# main.net
KiCad netlist of a schematic drawn in Altium Designer
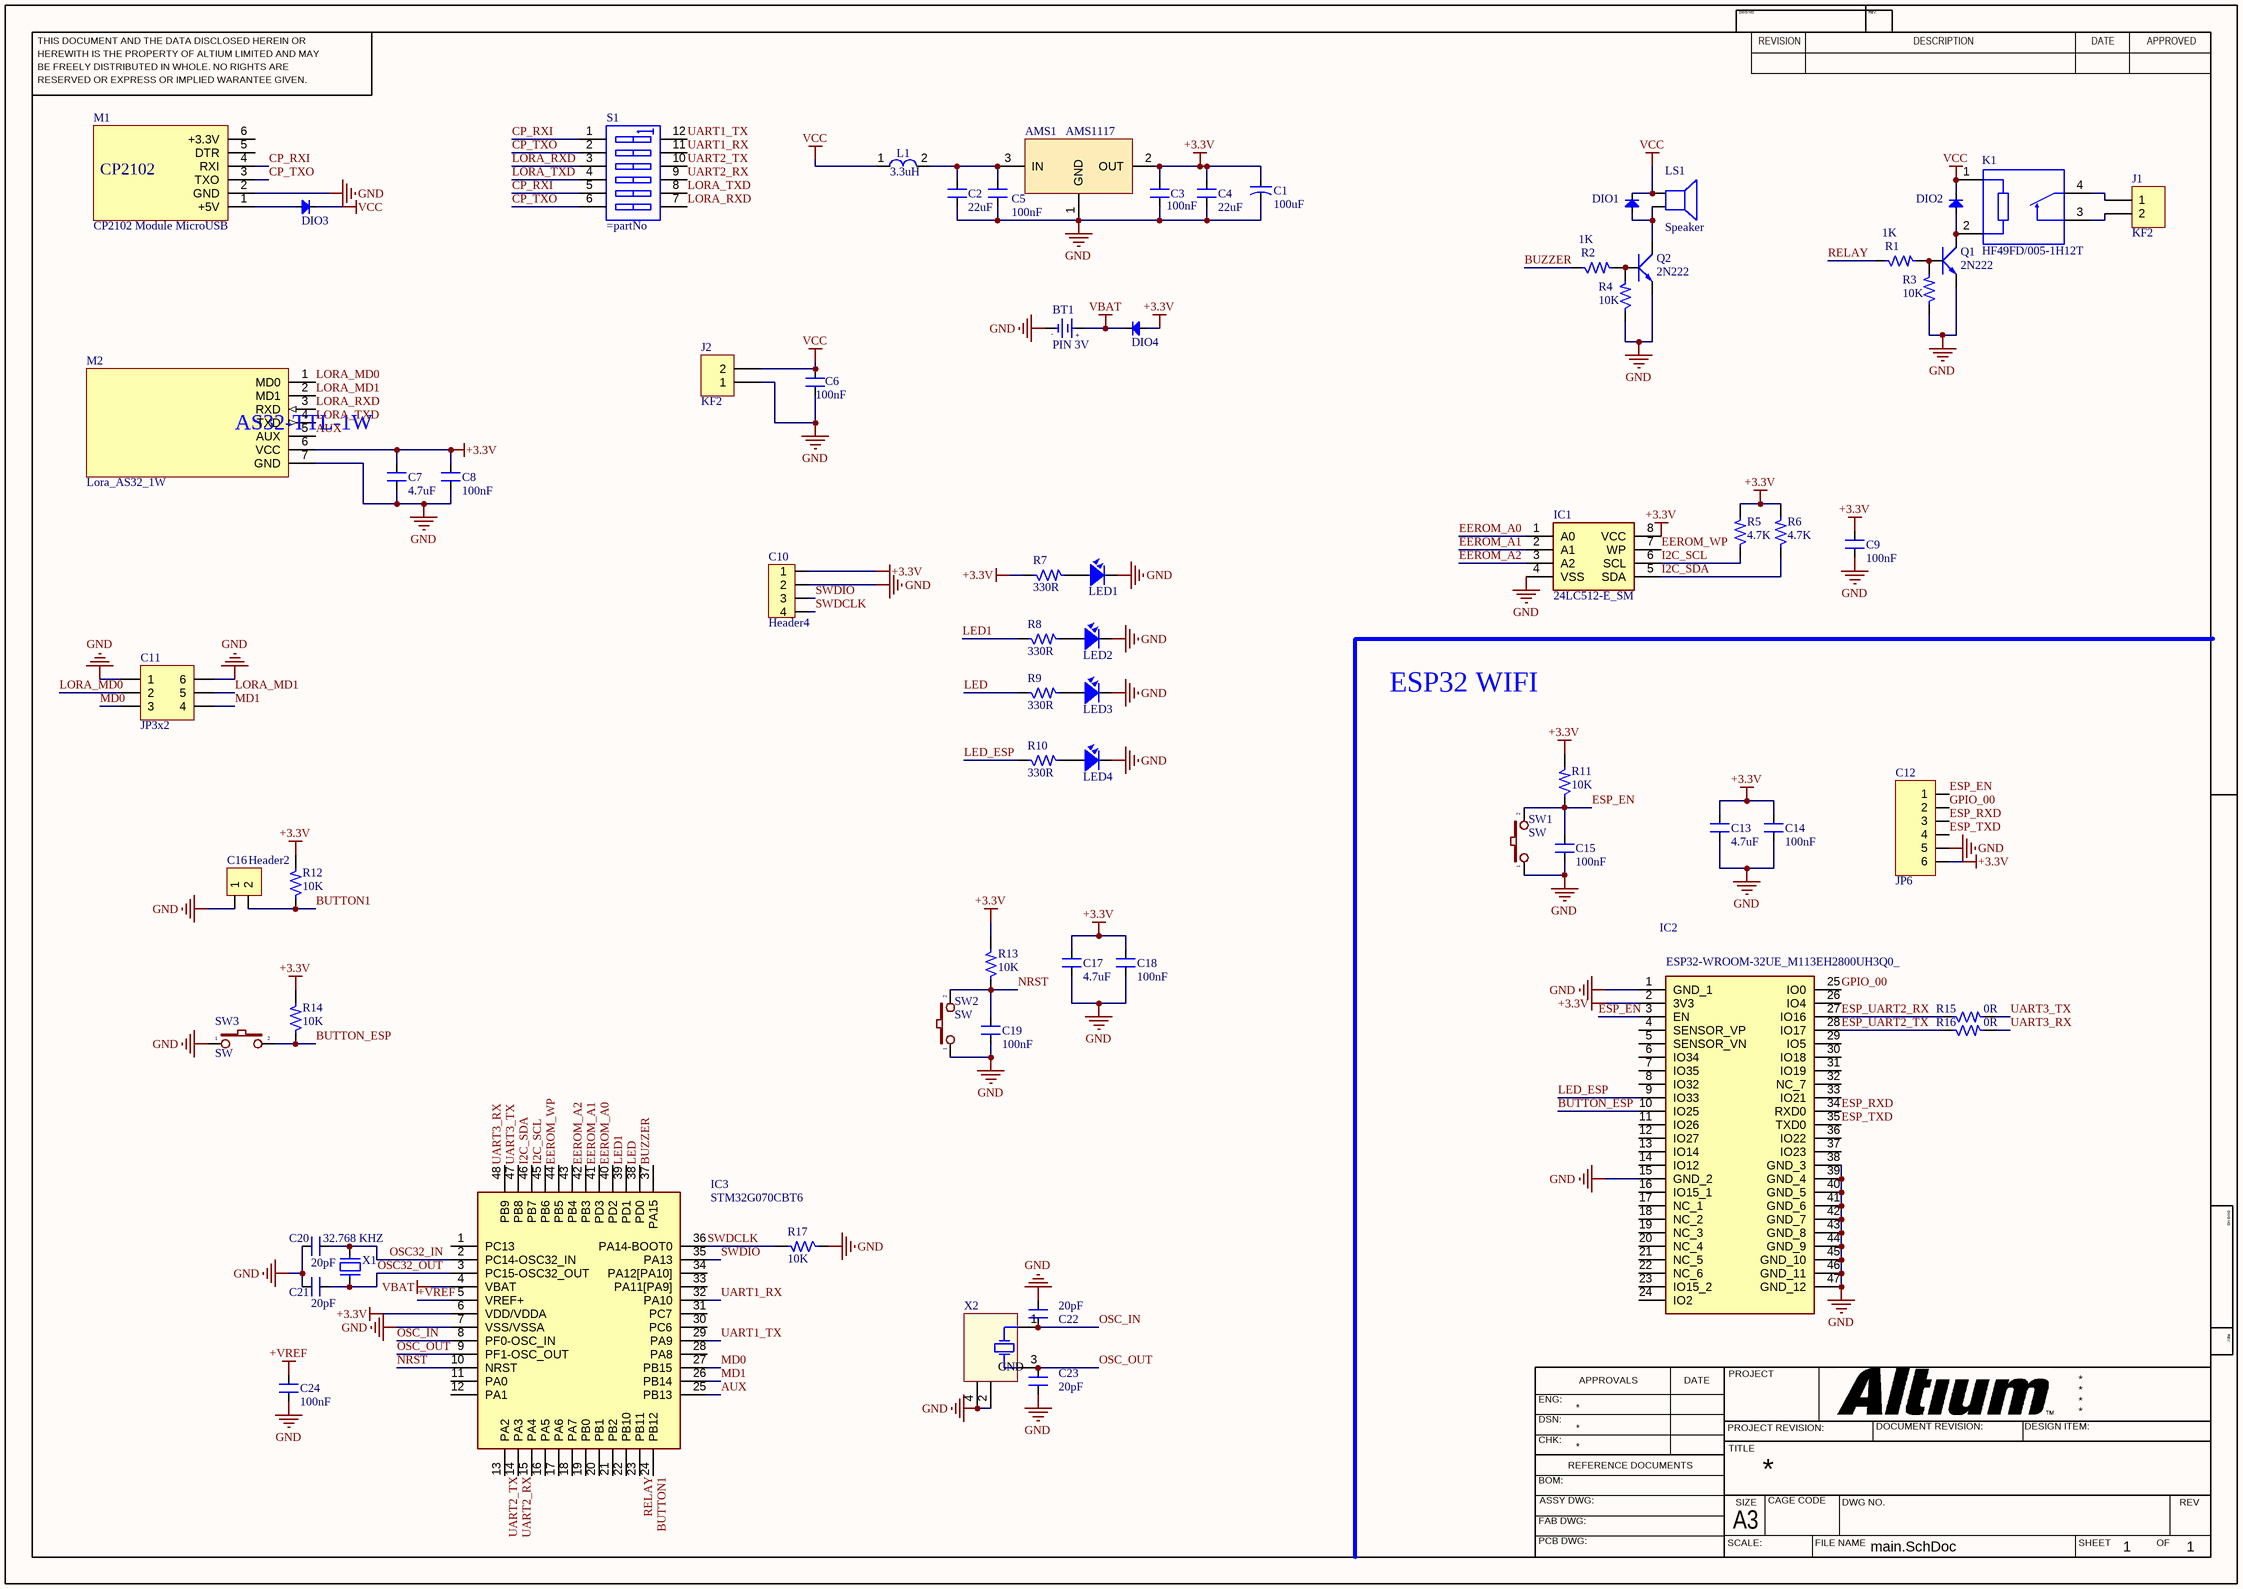
[diagram p0: main.SchDoc]

(export (version "E")
  (design (tool "Eeschema 10.0.6"))
  (components
    (comp (ref "AMS1") (value "AMS1117") (footprint "SOT223_N") (libsource (lib "SamacSys") (part "AMS1117")))
    (comp (ref "BT1")
      (value "PIN 3V")
      (footprint "PIN3V")
      (description "Battery 3VDC")
      (libsource (lib "LIBRARY") (part "PIN 3V"))
    )
    (comp (ref "C1")
      (value "100uF")
      (footprint "CA-ALU-5")
      (description "Capacitor (Semiconductor SIM Model)")
      (fields (field (name "PUBLISHER") "Altium Limited"))
      (libsource (lib "thu vien 3d") (part "CN-ALU-DIP"))
    )
    (comp (ref "C2")
      (value "22uF")
      (footprint "CAP_0805")
      (description "22µF ±20% 25V Ceramic Capacitor X5R 0805 (2012 Metric)")
      (fields
        (field (name "MANUFACTURER") "Murata Electronics")
        (field (name "MANUFACTURER PART NUMBER") "GRM21BR61E226ME44K")
      )
      (libsource (lib "EsteemPCB_SOM_Course_schlib") (part "CAP_22uF-25V-20%-0805"))
    )
    (comp (ref "C3")
      (value "100nF")
      (footprint "CAP_0603")
      (description "0.1µF ±10% 10V Ceramic Capacitor X7R 0603 (1608 Metric)")
      (fields
        (field (name "MANUFACTURER") "Yageo")
        (field (name "MANUFACTURER PART NUMBER") "CC0603KRX7R6BB104")
      )
      (libsource (lib "EsteemPCB_SOM_Course_schlib") (part "CAP_100nF-10V-5%-0603"))
    )
    (comp (ref "C4")
      (value "22uF")
      (footprint "CAP_0805")
      (description "22µF ±20% 25V Ceramic Capacitor X5R 0805 (2012 Metric)")
      (fields
        (field (name "MANUFACTURER") "Murata Electronics")
        (field (name "MANUFACTURER PART NUMBER") "GRM21BR61E226ME44K")
      )
      (libsource (lib "EsteemPCB_SOM_Course_schlib") (part "CAP_22uF-25V-20%-0805"))
    )
    (comp (ref "C5")
      (value "100nF")
      (footprint "CAP_0603")
      (description "0.1µF ±10% 10V Ceramic Capacitor X7R 0603 (1608 Metric)")
      (fields
        (field (name "MANUFACTURER") "Yageo")
        (field (name "MANUFACTURER PART NUMBER") "CC0603KRX7R6BB104")
      )
      (libsource (lib "EsteemPCB_SOM_Course_schlib") (part "CAP_100nF-10V-5%-0603"))
    )
    (comp (ref "C6") (value "100nF") (footprint "CN2.5") (libsource (lib "thu vien 3d") (part "CN")))
    (comp (ref "C7")
      (value "4.7uF")
      (footprint "CAP_0603")
      (description "4.7µF ±10% 16V Ceramic Capacitor X5R 0603 (1608 Metric)")
      (fields
        (field (name "MANUFACTURER") "Murata Electronics")
        (field (name "MANUFACTURER PART NUMBER") "GRM188R61C475KAAJD")
      )
      (libsource (lib "EsteemPCB_SOM_Course_schlib") (part "CAP_4.7uF-16V-10%-0603"))
    )
    (comp (ref "C8")
      (value "100nF")
      (footprint "CAP_0603")
      (description "0.1µF ±10% 10V Ceramic Capacitor X7R 0603 (1608 Metric)")
      (fields
        (field (name "MANUFACTURER") "Yageo")
        (field (name "MANUFACTURER PART NUMBER") "CC0603KRX7R6BB104")
      )
      (libsource (lib "EsteemPCB_SOM_Course_schlib") (part "CAP_100nF-10V-5%-0603"))
    )
    (comp (ref "C9")
      (value "100nF")
      (footprint "CAP_0603")
      (description "0.1µF ±10% 10V Ceramic Capacitor X7R 0603 (1608 Metric)")
      (fields
        (field (name "MANUFACTURER") "Yageo")
        (field (name "MANUFACTURER PART NUMBER") "CC0603KRX7R6BB104")
      )
      (libsource (lib "EsteemPCB_SOM_Course_schlib") (part "CAP_100nF-10V-5%-0603"))
    )
    (comp (ref "C10")
      (value "Header4")
      (footprint "Header4")
      (description "Header IDC, 4 x 1 Pin Vertical 2.54mm Pitch (Non-Boxed, Male)")
      (fields
        (field (name "MANUFACTURER") "Würth Elektronik eiSos GmbH")
        (field (name "PARTNO") "613002143121")
        (field (name "CREATED BY") "Karrer Zheng")
      )
      (libsource (lib "thu vien 3d") (part "Header4"))
    )
    (comp (ref "C11")
      (value "JP3x2")
      (footprint "JP3-D2T")
      (description "WR-PHD 2.54 mm Dual Socket Header")
      (fields
        (field (name "MANUFACTURER") "Würth Elektronik eiSos GmbH")
        (field (name "PARTNO") "61300621821")
        (field (name "CREATED BY") "Karrer Zheng")
      )
      (libsource (lib "thu vien 3d") (part "JP3x2"))
    )
    (comp (ref "C12")
      (value "JP6")
      (footprint "JP6-C1T")
      (description "WR-PHD 2.54 mm Angled Socket Header")
      (fields
        (field (name "MANUFACTURER") "Würth Elektronik eiSos GmbH")
        (field (name "PARTNO") "613006143121")
        (field (name "CREATED BY") "Karrer Zheng")
      )
      (libsource (lib "LIBRARY") (part "JP6"))
    )
    (comp (ref "C13")
      (value "4.7uF")
      (footprint "CAP_0603")
      (description "4.7µF ±10% 16V Ceramic Capacitor X5R 0603 (1608 Metric)")
      (fields
        (field (name "MANUFACTURER") "Murata Electronics")
        (field (name "MANUFACTURER PART NUMBER") "GRM188R61C475KAAJD")
      )
      (libsource (lib "EsteemPCB_SOM_Course_schlib") (part "CAP_4.7uF-16V-10%-0603"))
    )
    (comp (ref "C14")
      (value "100nF")
      (footprint "CAP_0603")
      (description "0.1µF ±10% 10V Ceramic Capacitor X7R 0603 (1608 Metric)")
      (fields
        (field (name "MANUFACTURER") "Yageo")
        (field (name "MANUFACTURER PART NUMBER") "CC0603KRX7R6BB104")
      )
      (libsource (lib "EsteemPCB_SOM_Course_schlib") (part "CAP_100nF-10V-5%-0603"))
    )
    (comp (ref "C15")
      (value "100nF")
      (footprint "CAP_0603")
      (description "0.1µF ±10% 10V Ceramic Capacitor X7R 0603 (1608 Metric)")
      (fields
        (field (name "MANUFACTURER") "Yageo")
        (field (name "MANUFACTURER PART NUMBER") "CC0603KRX7R6BB104")
      )
      (libsource (lib "EsteemPCB_SOM_Course_schlib") (part "CAP_100nF-10V-5%-0603"))
    )
    (comp (ref "C16")
      (value "Header2")
      (footprint "Header2")
      (description "Header IDC, 2 x 1 Pin Vertical 2.54mm Pitch (Non-Boxed, Male)")
      (fields
        (field (name "MANUFACTURER") "Würth Elektronik eiSos GmbH")
        (field (name "PARTNO") "613002143121")
        (field (name "CREATED BY") "Karrer Zheng")
      )
      (libsource (lib "LIBRARY") (part "Header2"))
    )
    (comp (ref "C17")
      (value "4.7uF")
      (footprint "CAP_0603")
      (description "4.7µF ±10% 16V Ceramic Capacitor X5R 0603 (1608 Metric)")
      (fields
        (field (name "MANUFACTURER") "Murata Electronics")
        (field (name "MANUFACTURER PART NUMBER") "GRM188R61C475KAAJD")
      )
      (libsource (lib "EsteemPCB_SOM_Course_schlib") (part "CAP_4.7uF-16V-10%-0603"))
    )
    (comp (ref "C18")
      (value "100nF")
      (footprint "CAP_0603")
      (description "0.1µF ±10% 10V Ceramic Capacitor X7R 0603 (1608 Metric)")
      (fields
        (field (name "MANUFACTURER") "Yageo")
        (field (name "MANUFACTURER PART NUMBER") "CC0603KRX7R6BB104")
      )
      (libsource (lib "EsteemPCB_SOM_Course_schlib") (part "CAP_100nF-10V-5%-0603"))
    )
    (comp (ref "C19")
      (value "100nF")
      (footprint "CAP_0603")
      (description "0.1µF ±10% 10V Ceramic Capacitor X7R 0603 (1608 Metric)")
      (fields
        (field (name "MANUFACTURER") "Yageo")
        (field (name "MANUFACTURER PART NUMBER") "CC0603KRX7R6BB104")
      )
      (libsource (lib "EsteemPCB_SOM_Course_schlib") (part "CAP_100nF-10V-5%-0603"))
    )
    (comp (ref "C20")
      (value "20pF")
      (footprint "CAP_0603")
      (description "1000pF ±10% 10V Ceramic Capacitor X7R 0603 (1608 Metric)")
      (fields
        (field (name "MANUFACTURER") "Yageo")
        (field (name "MANUFACTURER PART NUMBER") "CC0603KRX7R6BB102")
      )
      (libsource (lib "EsteemPCB_SOM_Course_schlib") (part "CAP_1nF-10V-10%-0603"))
    )
    (comp (ref "C21")
      (value "20pF")
      (footprint "CAP_0603")
      (description "1000pF ±10% 10V Ceramic Capacitor X7R 0603 (1608 Metric)")
      (fields
        (field (name "MANUFACTURER") "Yageo")
        (field (name "MANUFACTURER PART NUMBER") "CC0603KRX7R6BB102")
      )
      (libsource (lib "EsteemPCB_SOM_Course_schlib") (part "CAP_1nF-10V-10%-0603"))
    )
    (comp (ref "C22")
      (value "20pF")
      (footprint "CAP_0603")
      (description "1000pF ±10% 10V Ceramic Capacitor X7R 0603 (1608 Metric)")
      (fields
        (field (name "MANUFACTURER") "Yageo")
        (field (name "MANUFACTURER PART NUMBER") "CC0603KRX7R6BB102")
      )
      (libsource (lib "EsteemPCB_SOM_Course_schlib") (part "CAP_1nF-10V-10%-0603"))
    )
    (comp (ref "C23")
      (value "20pF")
      (footprint "CAP_0603")
      (description "1000pF ±10% 10V Ceramic Capacitor X7R 0603 (1608 Metric)")
      (fields
        (field (name "MANUFACTURER") "Yageo")
        (field (name "MANUFACTURER PART NUMBER") "CC0603KRX7R6BB102")
      )
      (libsource (lib "EsteemPCB_SOM_Course_schlib") (part "CAP_1nF-10V-10%-0603"))
    )
    (comp (ref "C24")
      (value "100nF")
      (footprint "CAP_0603")
      (description "0.1µF ±10% 10V Ceramic Capacitor X7R 0603 (1608 Metric)")
      (fields
        (field (name "MANUFACTURER") "Yageo")
        (field (name "MANUFACTURER PART NUMBER") "CC0603KRX7R6BB104")
      )
      (libsource (lib "EsteemPCB_SOM_Course_schlib") (part "CAP_100nF-10V-5%-0603"))
    )
    (comp (ref "DIO1")
      (value "Diode SMD")
      (footprint "DIO-SMD-123")
      (description "Default Diode")
      (fields (field (name "PUBLISHER") "Altium Limited"))
      (libsource (lib "LIBRARY") (part "Diode SMD"))
    )
    (comp (ref "DIO2")
      (value "Diode SMD")
      (footprint "DIO-SMD-123")
      (description "Default Diode")
      (fields (field (name "PUBLISHER") "Altium Limited"))
      (libsource (lib "LIBRARY") (part "Diode SMD"))
    )
    (comp (ref "DIO3")
      (value "Diode SMD")
      (footprint "DIO-SMD-123")
      (description "Default Diode")
      (fields (field (name "PUBLISHER") "Altium Limited"))
      (libsource (lib "LIBRARY") (part "Diode SMD"))
    )
    (comp (ref "DIO4")
      (value "Diode SMD")
      (footprint "DIO-SMD-123")
      (description "Default Diode")
      (fields (field (name "PUBLISHER") "Altium Limited"))
      (libsource (lib "LIBRARY") (part "Diode SMD"))
    )
    (comp (ref "IC1")
      (value "24LC512-E_SM")
      (footprint "SamacSys:SOIC127P794X203-8N")
      (description "Integrated Circuit")
      (fields
        (field (name "MANUFACTURER_PART_NUMBER") "24LC512-E/SM")
        (field (name "MOUSER PART NUMBER") "579-24LC512-E/SM")
      )
      (libsource (lib "*") (part "24LC512-E_SM"))
    )
    (comp (ref "IC2")
      (value "ESP32-WROOM-32UE_M113EH2800UH3Q0_")
      (footprint "SamacSys:ESP32WROOM32UEM113EH2800UH3Q0")
      (description "Integrated Circuit")
      (fields
        (field (name "MANUFACTURER_PART_NUMBER") "ESP32-WROOM-32UE(M113EH2800UH3Q0)")
        (field (name "MOUSER PART NUMBER") "356-ESP32WRM32UE28UH")
      )
      (libsource (lib "*") (part "ESP32-WROOM-32UE_M113EH2800UH3Q0_"))
    )
    (comp (ref "IC3")
      (value "STM32G070CBT6")
      (footprint "SamacSys:QFP50P900X900X160-48N")
      (description "Integrated Circuit")
      (fields (field (name "MOUSER PART NUMBER") "511-STM32G070CBT6"))
      (libsource (lib "*") (part "STM32G070CBT6"))
    )
    (comp (ref "J1")
      (value "KF2")
      (footprint "KF2-5.08")
      (fields
        (field (name "MANUFACTURER") "Würth Elektronik eiSos GmbH")
        (field (name "PARTNO") "691103110002")
        (field (name "CREATED BY") "Karrer Zheng")
      )
      (libsource (lib "") (part "KF2_1"))
    )
    (comp (ref "J2")
      (value "KF2")
      (footprint "KF2-5.08")
      (fields
        (field (name "MANUFACTURER") "Würth Elektronik eiSos GmbH")
        (field (name "PARTNO") "691103110002")
        (field (name "CREATED BY") "Karrer Zheng")
      )
      (libsource (lib "LIBRARY") (part "KF2"))
    )
    (comp (ref "K1")
      (value "HF49FD/005-1H12T")
      (footprint "RELAY_HF49FD/005-1H12T")
      (description "Relay: electromagnetic; SPST-NO; Ucoil: 5VDC; 5A/250VAC; 5A/30VDC")
      (fields (field (name "MF") "Hongfa"))
      (libsource (lib "HF49FD_005-1H12T") (part "HF49FD/005-1H12T"))
    )
    (comp (ref "L1")
      (value "3.3uH")
      (footprint "L-SMD-M-7.3x4.5")
      (fields
        (field (name "PARTNO") "78477010")
        (field (name "MANUFACTURER") "Wurth Elektronik")
        (field (name "CREATED BY") "Baojun Chen")
      )
      (libsource (lib "thu vien 3d") (part "L-SMD-1"))
    )
    (comp (ref "LED1")
      (value "LED")
      (footprint "LED-3MM-RED")
      (description "LED Single colour Green and Red")
      (libsource (lib "LIBRARY") (part "LED"))
    )
    (comp (ref "LED2")
      (value "LED")
      (footprint "LED-3MM-GREEN")
      (description "LED Single colour Green and Red")
      (libsource (lib "LIBRARY") (part "LED"))
    )
    (comp (ref "LED3")
      (value "LED")
      (footprint "LED-3MM-GREEN")
      (description "LED Single colour Green and Red")
      (libsource (lib "LIBRARY") (part "LED"))
    )
    (comp (ref "LED4")
      (value "LED")
      (footprint "LED-3MM-GREEN")
      (description "LED Single colour Green and Red")
      (libsource (lib "LIBRARY") (part "LED"))
    )
    (comp (ref "LS1")
      (value "Speaker")
      (footprint "SPEAKER")
      (description "Loudspeaker")
      (fields (field (name "PUBLISHER") "Altium Limited"))
      (libsource (lib "LIBRARY") (part "Speaker"))
    )
    (comp (ref "M1")
      (value "CP2102 Module MicroUSB")
      (footprint "CP2102 Module")
      (libsource (lib "SamacSys") (part "CP2102 Module MicroUSB"))
    )
    (comp (ref "M2")
      (value "Lora_AS32_1W")
      (footprint "LORA_AS32-TTL-1W")
      (libsource (lib "SamacSys") (part "Lora_AS32_1W"))
    )
    (comp (ref "Q1")
      (value "2N222")
      (footprint "SOT23-231")
      (description "NPN 600mW, ECB")
      (libsource (lib "LIBRARY") (part "2N222"))
    )
    (comp (ref "Q2")
      (value "2N222")
      (footprint "SOT23-231")
      (description "NPN 600mW, ECB")
      (libsource (lib "LIBRARY") (part "2N222"))
    )
    (comp (ref "R1")
      (value "1K")
      (footprint "RES_0603")
      (description "1 kOhms ±1% 0.1W, 1/10W Chip Resistor 0603 (1608 Metric) Thick Film")
      (fields
        (field (name "MANUFACTURER") "Yageo")
        (field (name "MANUFACTURER PART NUMBER") "RC0603FR-071KL")
      )
      (libsource (lib "EsteemPCB_SOM_Course_schlib") (part "RES_1K-0.1W-1%-0603"))
    )
    (comp (ref "R2")
      (value "1K")
      (footprint "RES_0603")
      (description "1 kOhms ±1% 0.1W, 1/10W Chip Resistor 0603 (1608 Metric) Thick Film")
      (fields
        (field (name "MANUFACTURER") "Yageo")
        (field (name "MANUFACTURER PART NUMBER") "RC0603FR-071KL")
      )
      (libsource (lib "EsteemPCB_SOM_Course_schlib") (part "RES_1K-0.1W-1%-0603"))
    )
    (comp (ref "R3")
      (value "10K")
      (footprint "RES_0603")
      (description "10 kOhms ±1% 0.1W, 1/10W Chip Resistor 0603 (1608 Metric) Thick Film")
      (fields
        (field (name "MANUFACTURER") "Yageo")
        (field (name "MANUFACTURER PART NUMBER") "RC0603FR-0710KL")
      )
      (libsource (lib "EsteemPCB_SOM_Course_schlib") (part "RES_10K-0.1W-1%-0603"))
    )
    (comp (ref "R4")
      (value "10K")
      (footprint "RES_0603")
      (description "10 kOhms ±1% 0.1W, 1/10W Chip Resistor 0603 (1608 Metric) Thick Film")
      (fields
        (field (name "MANUFACTURER") "Yageo")
        (field (name "MANUFACTURER PART NUMBER") "RC0603FR-0710KL")
      )
      (libsource (lib "EsteemPCB_SOM_Course_schlib") (part "RES_10K-0.1W-1%-0603"))
    )
    (comp (ref "R5")
      (value "4.7K")
      (footprint "RES_0603")
      (fields
        (field (name "MANUFACTURER") "Panasonic Electronic Components")
        (field (name "MANUFACTURER PART NUMBER") "ERJ-3RQF3R3V")
      )
      (libsource (lib "EsteemPCB_SOM_Course_schlib") (part "RES_3.3R-0.1W-1%-0603"))
    )
    (comp (ref "R6")
      (value "4.7K")
      (footprint "RES_0603")
      (fields
        (field (name "MANUFACTURER") "Panasonic Electronic Components")
        (field (name "MANUFACTURER PART NUMBER") "ERJ-3RQF3R3V")
      )
      (libsource (lib "EsteemPCB_SOM_Course_schlib") (part "RES_3.3R-0.1W-1%-0603"))
    )
    (comp (ref "R7")
      (value "330R")
      (footprint "RES_0603")
      (fields
        (field (name "MANUFACTURER") "Panasonic Electronic Components")
        (field (name "MANUFACTURER PART NUMBER") "ERJ-3RQF3R3V")
      )
      (libsource (lib "EsteemPCB_SOM_Course_schlib") (part "RES_3.3R-0.1W-1%-0603"))
    )
    (comp (ref "R8")
      (value "330R")
      (footprint "RES_0603")
      (fields
        (field (name "MANUFACTURER") "Panasonic Electronic Components")
        (field (name "MANUFACTURER PART NUMBER") "ERJ-3RQF3R3V")
      )
      (libsource (lib "EsteemPCB_SOM_Course_schlib") (part "RES_3.3R-0.1W-1%-0603"))
    )
    (comp (ref "R9")
      (value "330R")
      (footprint "RES_0603")
      (fields
        (field (name "MANUFACTURER") "Panasonic Electronic Components")
        (field (name "MANUFACTURER PART NUMBER") "ERJ-3RQF3R3V")
      )
      (libsource (lib "EsteemPCB_SOM_Course_schlib") (part "RES_3.3R-0.1W-1%-0603"))
    )
    (comp (ref "R10")
      (value "330R")
      (footprint "RES_0603")
      (fields
        (field (name "MANUFACTURER") "Panasonic Electronic Components")
        (field (name "MANUFACTURER PART NUMBER") "ERJ-3RQF3R3V")
      )
      (libsource (lib "EsteemPCB_SOM_Course_schlib") (part "RES_3.3R-0.1W-1%-0603"))
    )
    (comp (ref "R11")
      (value "10K")
      (footprint "RES_0603")
      (description "10 kOhms ±1% 0.1W, 1/10W Chip Resistor 0603 (1608 Metric) Thick Film")
      (fields
        (field (name "MANUFACTURER") "Yageo")
        (field (name "MANUFACTURER PART NUMBER") "RC0603FR-0710KL")
      )
      (libsource (lib "EsteemPCB_SOM_Course_schlib") (part "RES_10K-0.1W-1%-0603"))
    )
    (comp (ref "R12")
      (value "10K")
      (footprint "RES_0603")
      (description "10 kOhms ±1% 0.1W, 1/10W Chip Resistor 0603 (1608 Metric) Thick Film")
      (fields
        (field (name "MANUFACTURER") "Yageo")
        (field (name "MANUFACTURER PART NUMBER") "RC0603FR-0710KL")
      )
      (libsource (lib "EsteemPCB_SOM_Course_schlib") (part "RES_10K-0.1W-1%-0603"))
    )
    (comp (ref "R13")
      (value "10K")
      (footprint "RES_0603")
      (description "1 kOhms ±1% 0.1W, 1/10W Chip Resistor 0603 (1608 Metric) Thick Film")
      (fields
        (field (name "MANUFACTURER") "Yageo")
        (field (name "MANUFACTURER PART NUMBER") "RC0603FR-071KL")
      )
      (libsource (lib "EsteemPCB_SOM_Course_schlib") (part "RES_1K-0.1W-1%-0603"))
    )
    (comp (ref "R14")
      (value "10K")
      (footprint "RES_0603")
      (description "10 kOhms ±1% 0.1W, 1/10W Chip Resistor 0603 (1608 Metric) Thick Film")
      (fields
        (field (name "MANUFACTURER") "Yageo")
        (field (name "MANUFACTURER PART NUMBER") "RC0603FR-0710KL")
      )
      (libsource (lib "EsteemPCB_SOM_Course_schlib") (part "RES_10K-0.1W-1%-0603"))
    )
    (comp (ref "R15")
      (value "0R")
      (footprint "RES_0603")
      (description "0 Ohms Jumper 0.1W, 1/10W Chip Resistor 0603 (1608 Metric) Thick Film")
      (fields
        (field (name "MANUFACTURER") "Yageo")
        (field (name "MANUFACTURER PART NUMBER") "RC0603JR-070RL")
      )
      (libsource (lib "EsteemPCB_SOM_Course_schlib") (part "RES_0R-0.1W-1%-0603"))
    )
    (comp (ref "R16")
      (value "0R")
      (footprint "RES_0603")
      (description "0 Ohms Jumper 0.1W, 1/10W Chip Resistor 0603 (1608 Metric) Thick Film")
      (fields
        (field (name "MANUFACTURER") "Yageo")
        (field (name "MANUFACTURER PART NUMBER") "RC0603JR-070RL")
      )
      (libsource (lib "EsteemPCB_SOM_Course_schlib") (part "RES_0R-0.1W-1%-0603"))
    )
    (comp (ref "R17")
      (value "10K")
      (footprint "RES_0603")
      (description "1 kOhms ±1% 0.1W, 1/10W Chip Resistor 0603 (1608 Metric) Thick Film")
      (fields
        (field (name "MANUFACTURER") "Yageo")
        (field (name "MANUFACTURER PART NUMBER") "RC0603FR-071KL")
      )
      (libsource (lib "EsteemPCB_SOM_Course_schlib") (part "RES_1K-0.1W-1%-0603"))
    )
    (comp (ref "S1")
      (value "~")
      (footprint "SW-DIP6")
      (description "WS-DITV 2.54 mm small compact THT flat actuator with top tape")
      (fields
        (field (name "MANUFACTURER") "Wurth Elektronik")
        (field (name "PART NO.") "418127160906")
        (field (name "CREATED BY") "Baojun Chen")
      )
      (libsource (lib "LIBRARY") (part "SWDIP6"))
    )
    (comp (ref "SW1")
      (value "SW")
      (footprint "SW1-SMD")
      (description "Switch button 2 pin")
      (libsource (lib "LIBRARY") (part "SW2"))
    )
    (comp (ref "SW2")
      (value "SW")
      (footprint "SW1-SMD")
      (description "Switch button 2 pin")
      (libsource (lib "LIBRARY") (part "SW2"))
    )
    (comp (ref "SW3")
      (value "SW")
      (footprint "SW1-SMD")
      (description "Switch button 2 pin")
      (libsource (lib "LIBRARY") (part "SW2"))
    )
    (comp (ref "X1")
      (value "32.768 KHZ")
      (footprint "XT2-32.768KHz-2_V")
      (description "Crystal, 32.768 KHz, -40 to 85 degC, 3.2 x 1.5 x 0.9 mm SMD")
      (libsource (lib "LIBRARY") (part "XT2"))
    )
    (comp (ref "X2")
      (value "XT4")
      (footprint "XT4-16.000MHz-4_V")
      (description "Crystal, 16 MHz, -30 to 85 degC, 3.2 x 2.5 x 0.9 mm SMD")
      (libsource (lib "LIBRARY") (part "XT4"))
    )
  )
  (nets
    (net (code "1") (name "+3.3V") (class "Default")
      (node (ref "AMS1") (pin "2") (pinfunction "OUT_2") (pintype "passive"))
      (node (ref "C1") (pin "1") (pinfunction "1_1") (pintype "passive"))
      (node (ref "C10") (pin "1") (pinfunction "1_1") (pintype "passive"))
      (node (ref "C12") (pin "6") (pinfunction "6_6") (pintype "passive"))
      (node (ref "C13") (pin "2") (pinfunction "2_2") (pintype "passive"))
      (node (ref "C14") (pin "2") (pinfunction "2_2") (pintype "passive"))
      (node (ref "C17") (pin "2") (pinfunction "2_2") (pintype "passive"))
      (node (ref "C18") (pin "2") (pinfunction "2_2") (pintype "passive"))
      (node (ref "C3") (pin "2") (pinfunction "2_2") (pintype "passive"))
      (node (ref "C4") (pin "2") (pinfunction "2_2") (pintype "passive"))
      (node (ref "C7") (pin "2") (pinfunction "2_2") (pintype "passive"))
      (node (ref "C8") (pin "2") (pinfunction "2_2") (pintype "passive"))
      (node (ref "C9") (pin "2") (pinfunction "2_2") (pintype "passive"))
      (node (ref "DIO4") (pin "1") (pinfunction "A_1") (pintype "passive"))
      (node (ref "IC1") (pin "8") (pinfunction "VCC_8") (pintype "passive"))
      (node (ref "IC2") (pin "2") (pinfunction "3V3_2") (pintype "passive"))
      (node (ref "IC3") (pin "6") (pinfunction "VDD/VDDA_6") (pintype "passive"))
      (node (ref "M2") (pin "6") (pinfunction "VCC_6") (pintype "power_in"))
      (node (ref "R11") (pin "2") (pinfunction "2_2") (pintype "passive"))
      (node (ref "R12") (pin "2") (pinfunction "2_2") (pintype "passive"))
      (node (ref "R13") (pin "2") (pinfunction "2_2") (pintype "passive"))
      (node (ref "R14") (pin "2") (pinfunction "2_2") (pintype "passive"))
      (node (ref "R5") (pin "2") (pinfunction "2_2") (pintype "passive"))
      (node (ref "R6") (pin "2") (pinfunction "2_2") (pintype "passive"))
      (node (ref "R7") (pin "1") (pinfunction "1_1") (pintype "passive"))
    )
    (net (code "2") (name "+VREF") (class "Default")
      (node (ref "C24") (pin "2") (pinfunction "2_2") (pintype "passive"))
      (node (ref "IC3") (pin "5") (pinfunction "VREF+_5") (pintype "passive"))
    )
    (net (code "3") (name "/AUX") (class "Default")
      (node (ref "IC3") (pin "25") (pinfunction "PB13_25") (pintype "passive"))
      (node (ref "M2") (pin "5") (pinfunction "AUX_5") (pintype "passive"))
    )
    (net (code "4") (name "/BUTTON1") (class "Default")
      (node (ref "C16") (pin "2") (pinfunction "2_2") (pintype "passive"))
      (node (ref "IC3") (pin "24") (pinfunction "PB12_24") (pintype "passive"))
      (node (ref "R12") (pin "1") (pinfunction "1_1") (pintype "passive"))
    )
    (net (code "5") (name "/BUTTON_ESP") (class "Default")
      (node (ref "IC2") (pin "10") (pinfunction "IO25_10") (pintype "passive"))
      (node (ref "R14") (pin "1") (pinfunction "1_1") (pintype "passive"))
      (node (ref "SW3") (pin "2") (pinfunction "2_2") (pintype "passive"))
    )
    (net (code "6") (name "/BUZZER") (class "Default")
      (node (ref "IC3") (pin "37") (pinfunction "PA15_37") (pintype "passive"))
      (node (ref "R2") (pin "1") (pinfunction "1_1") (pintype "passive"))
    )
    (net (code "7") (name "/CP_RXI") (class "Default")
      (node (ref "M1") (pin "4") (pinfunction "RXI_4") (pintype "passive"))
      (node (ref "S1") (pin "1") (pinfunction "1_1") (pintype "passive"))
      (node (ref "S1") (pin "5") (pinfunction "5_5") (pintype "passive"))
    )
    (net (code "8") (name "/CP_TXO") (class "Default")
      (node (ref "M1") (pin "3") (pinfunction "TXO_3") (pintype "passive"))
      (node (ref "S1") (pin "2") (pinfunction "2_2") (pintype "passive"))
      (node (ref "S1") (pin "6") (pinfunction "6_6") (pintype "passive"))
    )
    (net (code "9") (name "/EEROM_A0") (class "Default")
      (node (ref "IC1") (pin "1") (pinfunction "A0_1") (pintype "passive"))
      (node (ref "IC3") (pin "40") (pinfunction "PD2_40") (pintype "passive"))
    )
    (net (code "10") (name "/EEROM_A1") (class "Default")
      (node (ref "IC1") (pin "2") (pinfunction "A1_2") (pintype "passive"))
      (node (ref "IC3") (pin "41") (pinfunction "PD3_41") (pintype "passive"))
    )
    (net (code "11") (name "/EEROM_A2") (class "Default")
      (node (ref "IC1") (pin "3") (pinfunction "A2_3") (pintype "passive"))
      (node (ref "IC3") (pin "42") (pinfunction "PB3_42") (pintype "passive"))
    )
    (net (code "12") (name "/EEROM_WP") (class "Default")
      (node (ref "IC1") (pin "7") (pinfunction "WP_7") (pintype "passive"))
      (node (ref "IC3") (pin "44") (pinfunction "PB5_44") (pintype "passive"))
    )
    (net (code "13") (name "/ESP_EN") (class "Default")
      (node (ref "C12") (pin "1") (pinfunction "1_1") (pintype "passive"))
      (node (ref "C15") (pin "2") (pinfunction "2_2") (pintype "passive"))
      (node (ref "IC2") (pin "3") (pinfunction "EN_3") (pintype "passive"))
      (node (ref "R11") (pin "1") (pinfunction "1_1") (pintype "passive"))
      (node (ref "SW1") (pin "2") (pinfunction "2_2") (pintype "passive"))
    )
    (net (code "14") (name "/ESP_RXD") (class "Default")
      (node (ref "C12") (pin "3") (pinfunction "3_3") (pintype "passive"))
      (node (ref "IC2") (pin "34") (pinfunction "RXD0_34") (pintype "passive"))
    )
    (net (code "15") (name "/ESP_TXD") (class "Default")
      (node (ref "C12") (pin "4") (pinfunction "4_4") (pintype "passive"))
      (node (ref "IC2") (pin "35") (pinfunction "TXD0_35") (pintype "passive"))
    )
    (net (code "16") (name "/ESP_UART2_RX") (class "Default")
      (node (ref "IC2") (pin "27") (pinfunction "IO16_27") (pintype "passive"))
      (node (ref "R15") (pin "1") (pinfunction "1_1") (pintype "passive"))
    )
    (net (code "17") (name "/ESP_UART2_TX") (class "Default")
      (node (ref "IC2") (pin "28") (pinfunction "IO17_28") (pintype "passive"))
      (node (ref "R16") (pin "1") (pinfunction "1_1") (pintype "passive"))
    )
    (net (code "18") (name "/GPIO_00") (class "Default")
      (node (ref "C12") (pin "2") (pinfunction "2_2") (pintype "passive"))
      (node (ref "IC2") (pin "25") (pinfunction "IO0_25") (pintype "passive"))
    )
    (net (code "19") (name "/I2C_SCL") (class "Default")
      (node (ref "IC1") (pin "6") (pinfunction "SCL_6") (pintype "passive"))
      (node (ref "IC3") (pin "45") (pinfunction "PB6_45") (pintype "passive"))
      (node (ref "R5") (pin "1") (pinfunction "1_1") (pintype "passive"))
    )
    (net (code "20") (name "/I2C_SDA") (class "Default")
      (node (ref "IC1") (pin "5") (pinfunction "SDA_5") (pintype "passive"))
      (node (ref "IC3") (pin "46") (pinfunction "PB7_46") (pintype "passive"))
      (node (ref "R6") (pin "1") (pinfunction "1_1") (pintype "passive"))
    )
    (net (code "21") (name "/LED") (class "Default")
      (node (ref "IC3") (pin "38") (pinfunction "PD0_38") (pintype "passive"))
      (node (ref "R9") (pin "1") (pinfunction "1_1") (pintype "passive"))
    )
    (net (code "22") (name "/LED1") (class "Default")
      (node (ref "IC3") (pin "39") (pinfunction "PD1_39") (pintype "passive"))
      (node (ref "R8") (pin "1") (pinfunction "1_1") (pintype "passive"))
    )
    (net (code "23") (name "/LED_ESP") (class "Default")
      (node (ref "IC2") (pin "9") (pinfunction "IO33_9") (pintype "passive"))
      (node (ref "R10") (pin "1") (pinfunction "1_1") (pintype "passive"))
    )
    (net (code "24") (name "/LORA_MD0") (class "Default")
      (node (ref "C11") (pin "2") (pinfunction "2_2") (pintype "passive"))
      (node (ref "M2") (pin "1") (pinfunction "MD0_1") (pintype "passive"))
    )
    (net (code "25") (name "/LORA_MD1") (class "Default")
      (node (ref "C11") (pin "5") (pinfunction "5_5") (pintype "passive"))
      (node (ref "M2") (pin "2") (pinfunction "MD1_2") (pintype "passive"))
    )
    (net (code "26") (name "/LORA_RXD") (class "Default")
      (node (ref "M2") (pin "3") (pinfunction "RXD_3") (pintype "input"))
      (node (ref "S1") (pin "3") (pinfunction "3_3") (pintype "passive"))
      (node (ref "S1") (pin "7") (pinfunction "7_7") (pintype "passive"))
    )
    (net (code "27") (name "/LORA_TXD") (class "Default")
      (node (ref "M2") (pin "4") (pinfunction "TXD_4") (pintype "output"))
      (node (ref "S1") (pin "4") (pinfunction "4_4") (pintype "passive"))
      (node (ref "S1") (pin "8") (pinfunction "8_8") (pintype "passive"))
    )
    (net (code "28") (name "/MD0") (class "Default")
      (node (ref "C11") (pin "3") (pinfunction "3_3") (pintype "passive"))
      (node (ref "IC3") (pin "27") (pinfunction "PB15_27") (pintype "passive"))
    )
    (net (code "29") (name "/MD1") (class "Default")
      (node (ref "C11") (pin "4") (pinfunction "4_4") (pintype "passive"))
      (node (ref "IC3") (pin "26") (pinfunction "PB14_26") (pintype "passive"))
    )
    (net (code "30") (name "/NRST") (class "Default")
      (node (ref "C19") (pin "2") (pinfunction "2_2") (pintype "passive"))
      (node (ref "IC3") (pin "10") (pinfunction "NRST_10") (pintype "passive"))
      (node (ref "R13") (pin "1") (pinfunction "1_1") (pintype "passive"))
      (node (ref "SW2") (pin "2") (pinfunction "2_2") (pintype "passive"))
    )
    (net (code "31") (name "/OSC32_IN") (class "Default")
      (node (ref "C20") (pin "2") (pinfunction "2_2") (pintype "passive"))
      (node (ref "IC3") (pin "2") (pinfunction "PC14-OSC32_IN_2") (pintype "passive"))
      (node (ref "X1") (pin "2") (pinfunction "2_2") (pintype "passive"))
    )
    (net (code "32") (name "/OSC32_OUT") (class "Default")
      (node (ref "C21") (pin "2") (pinfunction "2_2") (pintype "passive"))
      (node (ref "IC3") (pin "3") (pinfunction "PC15-OSC32_OUT_3") (pintype "passive"))
      (node (ref "X1") (pin "1") (pinfunction "1_1") (pintype "passive"))
    )
    (net (code "33") (name "/OSC_IN") (class "Default")
      (node (ref "C22") (pin "2") (pinfunction "2_2") (pintype "passive"))
      (node (ref "IC3") (pin "8") (pinfunction "PF0-OSC_IN_8") (pintype "passive"))
      (node (ref "X2") (pin "1") (pinfunction "XTAL_1") (pintype "passive"))
    )
    (net (code "34") (name "/OSC_OUT") (class "Default")
      (node (ref "C23") (pin "2") (pinfunction "2_2") (pintype "passive"))
      (node (ref "IC3") (pin "9") (pinfunction "PF1-OSC_OUT_9") (pintype "passive"))
      (node (ref "X2") (pin "3") (pinfunction "XTAL_3") (pintype "passive"))
    )
    (net (code "35") (name "/RELAY") (class "Default")
      (node (ref "IC3") (pin "23") (pinfunction "PB11_23") (pintype "passive"))
      (node (ref "R1") (pin "1") (pinfunction "1_1") (pintype "passive"))
    )
    (net (code "36") (name "/SWDCLK") (class "Default")
      (node (ref "C10") (pin "4") (pinfunction "4_4") (pintype "passive"))
      (node (ref "IC3") (pin "36") (pinfunction "PA14-BOOT0_36") (pintype "passive"))
      (node (ref "R17") (pin "2") (pinfunction "2_2") (pintype "passive"))
    )
    (net (code "37") (name "/SWDIO") (class "Default")
      (node (ref "C10") (pin "3") (pinfunction "3_3") (pintype "passive"))
      (node (ref "IC3") (pin "35") (pinfunction "PA13_35") (pintype "passive"))
    )
    (net (code "38") (name "/UART1_RX") (class "Default")
      (node (ref "IC3") (pin "32") (pinfunction "PA10_32") (pintype "passive"))
      (node (ref "S1") (pin "11") (pinfunction "11_11") (pintype "passive"))
    )
    (net (code "39") (name "/UART1_TX") (class "Default")
      (node (ref "IC3") (pin "29") (pinfunction "PA9_29") (pintype "passive"))
      (node (ref "S1") (pin "12") (pinfunction "12_12") (pintype "passive"))
    )
    (net (code "40") (name "/UART2_RX") (class "Default")
      (node (ref "IC3") (pin "14") (pinfunction "PA3_14") (pintype "passive"))
      (node (ref "S1") (pin "9") (pinfunction "9_9") (pintype "passive"))
    )
    (net (code "41") (name "/UART2_TX") (class "Default")
      (node (ref "IC3") (pin "13") (pinfunction "PA2_13") (pintype "passive"))
      (node (ref "S1") (pin "10") (pinfunction "10_10") (pintype "passive"))
    )
    (net (code "42") (name "/UART3_RX") (class "Default")
      (node (ref "IC3") (pin "48") (pinfunction "PB9_48") (pintype "passive"))
      (node (ref "R16") (pin "2") (pinfunction "2_2") (pintype "passive"))
    )
    (net (code "43") (name "/UART3_TX") (class "Default")
      (node (ref "IC3") (pin "47") (pinfunction "PB8_47") (pintype "passive"))
      (node (ref "R15") (pin "2") (pinfunction "2_2") (pintype "passive"))
    )
    (net (code "44") (name "GND") (class "Default")
      (node (ref "AMS1") (pin "1") (pinfunction "GND_1") (pintype "passive"))
      (node (ref "BT1") (pin "2") (pinfunction "GND_2") (pintype "passive"))
      (node (ref "C1") (pin "2") (pinfunction "2_2") (pintype "passive"))
      (node (ref "C10") (pin "2") (pinfunction "2_2") (pintype "passive"))
      (node (ref "C11") (pin "1") (pinfunction "1_1") (pintype "passive"))
      (node (ref "C11") (pin "6") (pinfunction "6_6") (pintype "passive"))
      (node (ref "C12") (pin "5") (pinfunction "5_5") (pintype "passive"))
      (node (ref "C13") (pin "1") (pinfunction "1_1") (pintype "passive"))
      (node (ref "C14") (pin "1") (pinfunction "1_1") (pintype "passive"))
      (node (ref "C15") (pin "1") (pinfunction "1_1") (pintype "passive"))
      (node (ref "C16") (pin "1") (pinfunction "1_1") (pintype "passive"))
      (node (ref "C17") (pin "1") (pinfunction "1_1") (pintype "passive"))
      (node (ref "C18") (pin "1") (pinfunction "1_1") (pintype "passive"))
      (node (ref "C19") (pin "1") (pinfunction "1_1") (pintype "passive"))
      (node (ref "C2") (pin "1") (pinfunction "1_1") (pintype "passive"))
      (node (ref "C20") (pin "1") (pinfunction "1_1") (pintype "passive"))
      (node (ref "C21") (pin "1") (pinfunction "1_1") (pintype "passive"))
      (node (ref "C22") (pin "1") (pinfunction "1_1") (pintype "passive"))
      (node (ref "C23") (pin "1") (pinfunction "1_1") (pintype "passive"))
      (node (ref "C24") (pin "1") (pinfunction "1_1") (pintype "passive"))
      (node (ref "C3") (pin "1") (pinfunction "1_1") (pintype "passive"))
      (node (ref "C4") (pin "1") (pinfunction "1_1") (pintype "passive"))
      (node (ref "C5") (pin "1") (pinfunction "1_1") (pintype "passive"))
      (node (ref "C6") (pin "1") (pinfunction "1_1") (pintype "passive"))
      (node (ref "C7") (pin "1") (pinfunction "1_1") (pintype "passive"))
      (node (ref "C8") (pin "1") (pinfunction "1_1") (pintype "passive"))
      (node (ref "C9") (pin "1") (pinfunction "1_1") (pintype "passive"))
      (node (ref "IC1") (pin "4") (pinfunction "VSS_4") (pintype "passive"))
      (node (ref "IC2") (pin "1") (pinfunction "GND_1_1") (pintype "passive"))
      (node (ref "IC2") (pin "15") (pinfunction "GND_2_15") (pintype "passive"))
      (node (ref "IC2") (pin "38") (pinfunction "GND_3_38") (pintype "passive"))
      (node (ref "IC2") (pin "39") (pinfunction "GND_4_39") (pintype "passive"))
      (node (ref "IC2") (pin "40") (pinfunction "GND_5_40") (pintype "passive"))
      (node (ref "IC2") (pin "41") (pinfunction "GND_6_41") (pintype "passive"))
      (node (ref "IC2") (pin "42") (pinfunction "GND_7_42") (pintype "passive"))
      (node (ref "IC2") (pin "43") (pinfunction "GND_8_43") (pintype "passive"))
      (node (ref "IC2") (pin "44") (pinfunction "GND_9_44") (pintype "passive"))
      (node (ref "IC2") (pin "45") (pinfunction "GND_10_45") (pintype "passive"))
      (node (ref "IC2") (pin "46") (pinfunction "GND_11_46") (pintype "passive"))
      (node (ref "IC2") (pin "47") (pinfunction "GND_12_47") (pintype "passive"))
      (node (ref "IC3") (pin "7") (pinfunction "VSS/VSSA_7") (pintype "passive"))
      (node (ref "J2") (pin "1") (pinfunction "1_1") (pintype "passive"))
      (node (ref "LED1") (pin "2") (pinfunction "2_2") (pintype "passive"))
      (node (ref "LED2") (pin "2") (pinfunction "2_2") (pintype "passive"))
      (node (ref "LED3") (pin "2") (pinfunction "2_2") (pintype "passive"))
      (node (ref "LED4") (pin "2") (pinfunction "2_2") (pintype "passive"))
      (node (ref "M1") (pin "2") (pinfunction "GND_2") (pintype "passive"))
      (node (ref "M2") (pin "7") (pinfunction "GND_7") (pintype "power_in"))
      (node (ref "Q1") (pin "1") (pinfunction "E_1") (pintype "passive"))
      (node (ref "Q2") (pin "1") (pinfunction "E_1") (pintype "passive"))
      (node (ref "R17") (pin "1") (pinfunction "1_1") (pintype "passive"))
      (node (ref "R3") (pin "1") (pinfunction "1_1") (pintype "passive"))
      (node (ref "R4") (pin "1") (pinfunction "1_1") (pintype "passive"))
      (node (ref "SW1") (pin "1") (pinfunction "1_1") (pintype "passive"))
      (node (ref "SW2") (pin "1") (pinfunction "1_1") (pintype "passive"))
      (node (ref "SW3") (pin "1") (pinfunction "1_1") (pintype "passive"))
      (node (ref "X2") (pin "2") (pinfunction "GND_2") (pintype "power_in"))
      (node (ref "X2") (pin "4") (pinfunction "GND_4") (pintype "power_in"))
    )
    (net (code "45") (name "Net-(AMS1-IN)") (class "Default")
      (node (ref "AMS1") (pin "3") (pinfunction "IN_3") (pintype "passive"))
      (node (ref "C2") (pin "2") (pinfunction "2_2") (pintype "passive"))
      (node (ref "C5") (pin "2") (pinfunction "2_2") (pintype "passive"))
      (node (ref "L1") (pin "2") (pinfunction "2_2") (pintype "passive"))
    )
    (net (code "46") (name "Net-(DIO1-A)") (class "Default")
      (node (ref "DIO1") (pin "1") (pinfunction "A_1") (pintype "passive"))
      (node (ref "LS1") (pin "2") (pinfunction "2_2") (pintype "passive"))
      (node (ref "Q2") (pin "3") (pinfunction "C_3") (pintype "passive"))
    )
    (net (code "47") (name "Net-(DIO2-A)") (class "Default")
      (node (ref "DIO2") (pin "1") (pinfunction "A_1") (pintype "passive"))
      (node (ref "K1") (pin "2") (pinfunction "L2_2") (pintype "passive"))
      (node (ref "Q1") (pin "3") (pinfunction "C_3") (pintype "passive"))
    )
    (net (code "48") (name "Net-(DIO3-A)") (class "Default")
      (node (ref "DIO3") (pin "1") (pinfunction "A_1") (pintype "passive"))
      (node (ref "M1") (pin "1") (pinfunction "+5V_1") (pintype "passive"))
    )
    (net (code "49") (name "Net-(K1-C1)") (class "Default")
      (node (ref "J1") (pin "1") (pinfunction "1_1") (pintype "passive"))
      (node (ref "K1") (pin "4") (pinfunction "C1_4") (pintype "passive"))
    )
    (net (code "50") (name "Net-(K1-C2)") (class "Default")
      (node (ref "J1") (pin "2") (pinfunction "2_2") (pintype "passive"))
      (node (ref "K1") (pin "3") (pinfunction "C2_3") (pintype "passive"))
    )
    (net (code "51") (name "Net-(LED1-Pad1)") (class "Default")
      (node (ref "LED1") (pin "1") (pinfunction "1_1") (pintype "passive"))
      (node (ref "R7") (pin "2") (pinfunction "2_2") (pintype "passive"))
    )
    (net (code "52") (name "Net-(LED2-Pad1)") (class "Default")
      (node (ref "LED2") (pin "1") (pinfunction "1_1") (pintype "passive"))
      (node (ref "R8") (pin "2") (pinfunction "2_2") (pintype "passive"))
    )
    (net (code "53") (name "Net-(LED3-Pad1)") (class "Default")
      (node (ref "LED3") (pin "1") (pinfunction "1_1") (pintype "passive"))
      (node (ref "R9") (pin "2") (pinfunction "2_2") (pintype "passive"))
    )
    (net (code "54") (name "Net-(LED4-Pad1)") (class "Default")
      (node (ref "LED4") (pin "1") (pinfunction "1_1") (pintype "passive"))
      (node (ref "R10") (pin "2") (pinfunction "2_2") (pintype "passive"))
    )
    (net (code "55") (name "Net-(Q1-B)") (class "Default")
      (node (ref "Q1") (pin "2") (pinfunction "B_2") (pintype "passive"))
      (node (ref "R1") (pin "2") (pinfunction "2_2") (pintype "passive"))
      (node (ref "R3") (pin "2") (pinfunction "2_2") (pintype "passive"))
    )
    (net (code "56") (name "Net-(Q2-B)") (class "Default")
      (node (ref "Q2") (pin "2") (pinfunction "B_2") (pintype "passive"))
      (node (ref "R2") (pin "2") (pinfunction "2_2") (pintype "passive"))
      (node (ref "R4") (pin "2") (pinfunction "2_2") (pintype "passive"))
    )
    (net (code "57") (name "VBAT") (class "Default")
      (node (ref "BT1") (pin "1") (pinfunction "+3V_1") (pintype "passive"))
      (node (ref "DIO4") (pin "2") (pinfunction "K_2") (pintype "passive"))
      (node (ref "IC3") (pin "4") (pinfunction "VBAT_4") (pintype "passive"))
    )
    (net (code "58") (name "VCC") (class "Default")
      (node (ref "C6") (pin "2") (pinfunction "2_2") (pintype "passive"))
      (node (ref "DIO1") (pin "2") (pinfunction "K_2") (pintype "passive"))
      (node (ref "DIO2") (pin "2") (pinfunction "K_2") (pintype "passive"))
      (node (ref "DIO3") (pin "2") (pinfunction "K_2") (pintype "passive"))
      (node (ref "J2") (pin "2") (pinfunction "2_2") (pintype "passive"))
      (node (ref "K1") (pin "1") (pinfunction "L1_1") (pintype "passive"))
      (node (ref "L1") (pin "1") (pinfunction "1_1") (pintype "passive"))
      (node (ref "LS1") (pin "1") (pinfunction "1_1") (pintype "passive"))
    )
    (net (code "59") (name "unconnected-(IC2-IO2-Pad24)") (class "Default")
      (node (ref "IC2") (pin "24") (pinfunction "IO2_24") (pintype "passive"))
    )
    (net (code "60") (name "unconnected-(IC2-IO4-Pad26)") (class "Default")
      (node (ref "IC2") (pin "26") (pinfunction "IO4_26") (pintype "passive"))
    )
    (net (code "61") (name "unconnected-(IC2-IO5-Pad29)") (class "Default")
      (node (ref "IC2") (pin "29") (pinfunction "IO5_29") (pintype "passive"))
    )
    (net (code "62") (name "unconnected-(IC2-IO12-Pad14)") (class "Default")
      (node (ref "IC2") (pin "14") (pinfunction "IO12_14") (pintype "passive"))
    )
    (net (code "63") (name "unconnected-(IC2-IO14-Pad13)") (class "Default")
      (node (ref "IC2") (pin "13") (pinfunction "IO14_13") (pintype "passive"))
    )
    (net (code "64") (name "unconnected-(IC2-IO15_1-Pad16)") (class "Default")
      (node (ref "IC2") (pin "16") (pinfunction "IO15_1_16") (pintype "passive"))
    )
    (net (code "65") (name "unconnected-(IC2-IO15_2-Pad23)") (class "Default")
      (node (ref "IC2") (pin "23") (pinfunction "IO15_2_23") (pintype "passive"))
    )
    (net (code "66") (name "unconnected-(IC2-IO18-Pad30)") (class "Default")
      (node (ref "IC2") (pin "30") (pinfunction "IO18_30") (pintype "passive"))
    )
    (net (code "67") (name "unconnected-(IC2-IO19-Pad31)") (class "Default")
      (node (ref "IC2") (pin "31") (pinfunction "IO19_31") (pintype "passive"))
    )
    (net (code "68") (name "unconnected-(IC2-IO21-Pad33)") (class "Default")
      (node (ref "IC2") (pin "33") (pinfunction "IO21_33") (pintype "passive"))
    )
    (net (code "69") (name "unconnected-(IC2-IO22-Pad36)") (class "Default")
      (node (ref "IC2") (pin "36") (pinfunction "IO22_36") (pintype "passive"))
    )
    (net (code "70") (name "unconnected-(IC2-IO23-Pad37)") (class "Default")
      (node (ref "IC2") (pin "37") (pinfunction "IO23_37") (pintype "passive"))
    )
    (net (code "71") (name "unconnected-(IC2-IO26-Pad11)") (class "Default")
      (node (ref "IC2") (pin "11") (pinfunction "IO26_11") (pintype "passive"))
    )
    (net (code "72") (name "unconnected-(IC2-IO27-Pad12)") (class "Default")
      (node (ref "IC2") (pin "12") (pinfunction "IO27_12") (pintype "passive"))
    )
    (net (code "73") (name "unconnected-(IC2-IO32-Pad8)") (class "Default")
      (node (ref "IC2") (pin "8") (pinfunction "IO32_8") (pintype "passive"))
    )
    (net (code "74") (name "unconnected-(IC2-IO34-Pad6)") (class "Default")
      (node (ref "IC2") (pin "6") (pinfunction "IO34_6") (pintype "passive"))
    )
    (net (code "75") (name "unconnected-(IC2-IO35-Pad7)") (class "Default")
      (node (ref "IC2") (pin "7") (pinfunction "IO35_7") (pintype "passive"))
    )
    (net (code "76") (name "unconnected-(IC2-NC_1-Pad17)") (class "Default")
      (node (ref "IC2") (pin "17") (pinfunction "NC_1_17") (pintype "passive"))
    )
    (net (code "77") (name "unconnected-(IC2-NC_2-Pad18)") (class "Default")
      (node (ref "IC2") (pin "18") (pinfunction "NC_2_18") (pintype "passive"))
    )
    (net (code "78") (name "unconnected-(IC2-NC_3-Pad19)") (class "Default")
      (node (ref "IC2") (pin "19") (pinfunction "NC_3_19") (pintype "passive"))
    )
    (net (code "79") (name "unconnected-(IC2-NC_4-Pad20)") (class "Default")
      (node (ref "IC2") (pin "20") (pinfunction "NC_4_20") (pintype "passive"))
    )
    (net (code "80") (name "unconnected-(IC2-NC_5-Pad21)") (class "Default")
      (node (ref "IC2") (pin "21") (pinfunction "NC_5_21") (pintype "passive"))
    )
    (net (code "81") (name "unconnected-(IC2-NC_6-Pad22)") (class "Default")
      (node (ref "IC2") (pin "22") (pinfunction "NC_6_22") (pintype "passive"))
    )
    (net (code "82") (name "unconnected-(IC2-NC_7-Pad32)") (class "Default")
      (node (ref "IC2") (pin "32") (pinfunction "NC_7_32") (pintype "passive"))
    )
    (net (code "83") (name "unconnected-(IC2-SENSOR_VN-Pad5)") (class "Default")
      (node (ref "IC2") (pin "5") (pinfunction "SENSOR_VN_5") (pintype "passive"))
    )
    (net (code "84") (name "unconnected-(IC2-SENSOR_VP-Pad4)") (class "Default")
      (node (ref "IC2") (pin "4") (pinfunction "SENSOR_VP_4") (pintype "passive"))
    )
    (net (code "85") (name "unconnected-(IC3-PA0-Pad11)") (class "Default")
      (node (ref "IC3") (pin "11") (pinfunction "PA0_11") (pintype "passive"))
    )
    (net (code "86") (name "unconnected-(IC3-PA1-Pad12)") (class "Default")
      (node (ref "IC3") (pin "12") (pinfunction "PA1_12") (pintype "passive"))
    )
    (net (code "87") (name "unconnected-(IC3-PA4-Pad15)") (class "Default")
      (node (ref "IC3") (pin "15") (pinfunction "PA4_15") (pintype "passive"))
    )
    (net (code "88") (name "unconnected-(IC3-PA5-Pad16)") (class "Default")
      (node (ref "IC3") (pin "16") (pinfunction "PA5_16") (pintype "passive"))
    )
    (net (code "89") (name "unconnected-(IC3-PA6-Pad17)") (class "Default")
      (node (ref "IC3") (pin "17") (pinfunction "PA6_17") (pintype "passive"))
    )
    (net (code "90") (name "unconnected-(IC3-PA7-Pad18)") (class "Default")
      (node (ref "IC3") (pin "18") (pinfunction "PA7_18") (pintype "passive"))
    )
    (net (code "91") (name "unconnected-(IC3-PA8-Pad28)") (class "Default")
      (node (ref "IC3") (pin "28") (pinfunction "PA8_28") (pintype "passive"))
    )
    (net (code "92") (name "unconnected-(IC3-PA11[PA9]-Pad33)") (class "Default")
      (node (ref "IC3") (pin "33") (pinfunction "PA11[PA9]_33") (pintype "passive"))
    )
    (net (code "93") (name "unconnected-(IC3-PA12[PA10]-Pad34)") (class "Default")
      (node (ref "IC3") (pin "34") (pinfunction "PA12[PA10]_34") (pintype "passive"))
    )
    (net (code "94") (name "unconnected-(IC3-PB0-Pad19)") (class "Default")
      (node (ref "IC3") (pin "19") (pinfunction "PB0_19") (pintype "passive"))
    )
    (net (code "95") (name "unconnected-(IC3-PB1-Pad20)") (class "Default")
      (node (ref "IC3") (pin "20") (pinfunction "PB1_20") (pintype "passive"))
    )
    (net (code "96") (name "unconnected-(IC3-PB2-Pad21)") (class "Default")
      (node (ref "IC3") (pin "21") (pinfunction "PB2_21") (pintype "passive"))
    )
    (net (code "97") (name "unconnected-(IC3-PB4-Pad43)") (class "Default")
      (node (ref "IC3") (pin "43") (pinfunction "PB4_43") (pintype "passive"))
    )
    (net (code "98") (name "unconnected-(IC3-PB10-Pad22)") (class "Default")
      (node (ref "IC3") (pin "22") (pinfunction "PB10_22") (pintype "passive"))
    )
    (net (code "99") (name "unconnected-(IC3-PC6-Pad30)") (class "Default")
      (node (ref "IC3") (pin "30") (pinfunction "PC6_30") (pintype "passive"))
    )
    (net (code "100") (name "unconnected-(IC3-PC7-Pad31)") (class "Default")
      (node (ref "IC3") (pin "31") (pinfunction "PC7_31") (pintype "passive"))
    )
    (net (code "101") (name "unconnected-(IC3-PC13-Pad1)") (class "Default")
      (node (ref "IC3") (pin "1") (pinfunction "PC13_1") (pintype "passive"))
    )
    (net (code "102") (name "unconnected-(M1-+3.3V-Pad6)") (class "Default")
      (node (ref "M1") (pin "6") (pinfunction "+3.3V_6") (pintype "passive"))
    )
    (net (code "103") (name "unconnected-(M1-DTR-Pad5)") (class "Default")
      (node (ref "M1") (pin "5") (pinfunction "DTR_5") (pintype "passive"))
    )
  )
)
